# GPIO_Expander.net
KiCad netlist of a schematic drawn in Altium Designer
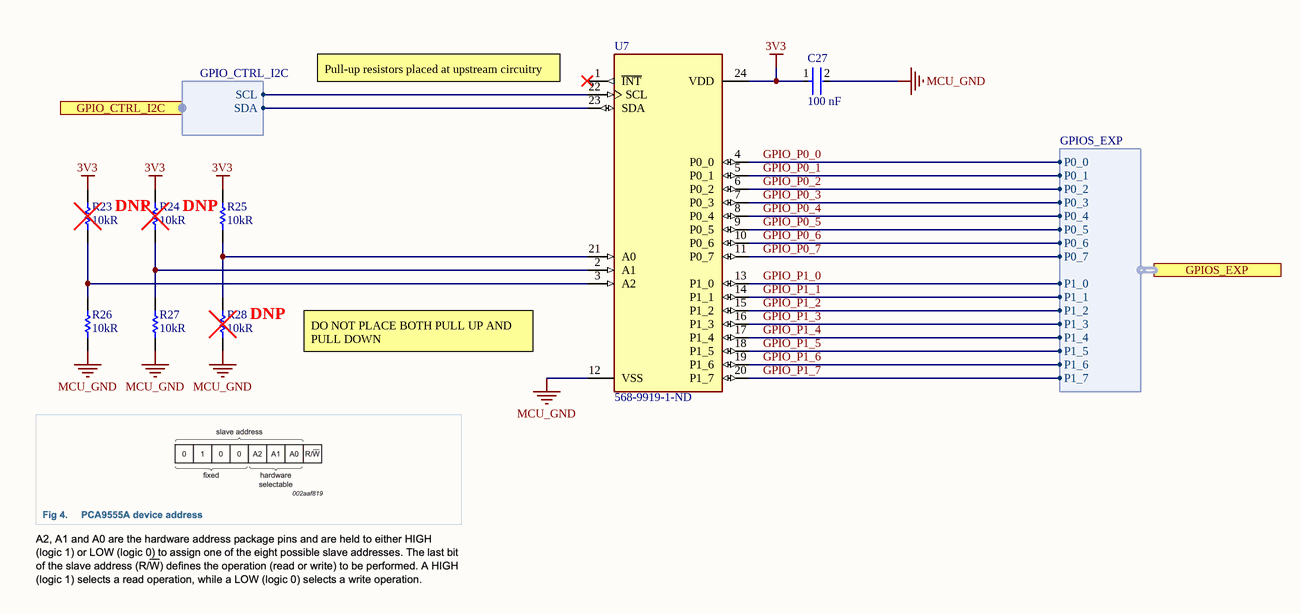
[diagram p0: GPIO_Expander.SchDoc]

(export (version "E")
  (design (tool "Eeschema 10.0.6"))
  (components
    (comp (ref "C27")
      (value "CC0603KRX7R7BB104")
      (footprint "FP-CC0603-DA-MFG")
      (description "CAP CER 0.1UF 16V X7R 0603")
      (fields
        (field (name "OCTOPART") "https://octopart.com/cc0603krx7r7bb104-yageo-192941")
        (field (name "TOLERANCE") "0.1")
        (field (name "CAPACITANCE") "100 nF")
      )
      (libsource (lib "Altium Content Vault") (part "11868f565c42a9108669ba33697ecf6"))
    )
    (comp (ref "R23")
      (value "CRCW060310K0FKEA")
      (footprint "RESC1609X50X30NL8T20")
      (description "Chip Resistor, 10 KOhm, +/- 1%, 100 mW, -55 to 155 degC, 0603 (1608 Metric), RoHS, Tape and Reel")
      (fields (field (name "MANUFACTURER") "Vishay Semiconductor") (field (name "RESISTANCE") "10kR"))
      (libsource (lib "Altium Content Vault") (part "RES-2"))
    )
    (comp (ref "R24")
      (value "CRCW060310K0FKEA")
      (footprint "RESC1609X50X30NL8T20")
      (description "Chip Resistor, 10 KOhm, +/- 1%, 100 mW, -55 to 155 degC, 0603 (1608 Metric), RoHS, Tape and Reel")
      (fields (field (name "MANUFACTURER") "Vishay Semiconductor") (field (name "RESISTANCE") "10kR"))
      (libsource (lib "Altium Content Vault") (part "RES-2"))
    )
    (comp (ref "R25")
      (value "CRCW060310K0FKEA")
      (footprint "RESC1609X50X30NL8T20")
      (description "Chip Resistor, 10 KOhm, +/- 1%, 100 mW, -55 to 155 degC, 0603 (1608 Metric), RoHS, Tape and Reel")
      (fields (field (name "MANUFACTURER") "Vishay Semiconductor") (field (name "RESISTANCE") "10kR"))
      (libsource (lib "Altium Content Vault") (part "RES-2"))
    )
    (comp (ref "R26")
      (value "CRCW060310K0FKEA")
      (footprint "RESC1609X50X30NL8T20")
      (description "Chip Resistor, 10 KOhm, +/- 1%, 100 mW, -55 to 155 degC, 0603 (1608 Metric), RoHS, Tape and Reel")
      (fields (field (name "MANUFACTURER") "Vishay Semiconductor") (field (name "RESISTANCE") "10kR"))
      (libsource (lib "Altium Content Vault") (part "RES-2"))
    )
    (comp (ref "R27")
      (value "CRCW060310K0FKEA")
      (footprint "RESC1609X50X30NL8T20")
      (description "Chip Resistor, 10 KOhm, +/- 1%, 100 mW, -55 to 155 degC, 0603 (1608 Metric), RoHS, Tape and Reel")
      (fields (field (name "MANUFACTURER") "Vishay Semiconductor") (field (name "RESISTANCE") "10kR"))
      (libsource (lib "Altium Content Vault") (part "RES-2"))
    )
    (comp (ref "R28")
      (value "CRCW060310K0FKEA")
      (footprint "RESC1609X50X30NL8T20")
      (description "Chip Resistor, 10 KOhm, +/- 1%, 100 mW, -55 to 155 degC, 0603 (1608 Metric), RoHS, Tape and Reel")
      (fields (field (name "MANUFACTURER") "Vishay Semiconductor") (field (name "RESISTANCE") "10kR"))
      (libsource (lib "Altium Content Vault") (part "RES-2"))
    )
    (comp (ref "U7")
      (value "568-9919-1-ND")
      (footprint "SOP65P640X110-24N")
      (description "Parallel I/O Port, 16-Bit, 16 I/O, CMOS, PDSO24")
      (fields
        (field (name "MANUFACTURER") "NXP Semiconductors")
        (field (name "MANUFACTURER PART NUMBER") "PCA9555APW,118")
        (field (name "SUPPLIER PART NUMBER 1") "568-9919-1-ND")
      )
      (libsource (lib "Schlib2") (part "PCA9555APW,118"))
    )
  )
  (nets
    (net (code "3") (name "/GPIO_P0_0") (class "Default")
      (node (ref "U7") (pin "4") (pinfunction "P0_0_4") (pintype "bidirectional"))
    )
    (net (code "4") (name "/GPIO_P0_1") (class "Default")
      (node (ref "U7") (pin "5") (pinfunction "P0_1_5") (pintype "bidirectional"))
    )
    (net (code "5") (name "/GPIO_P0_2") (class "Default")
      (node (ref "U7") (pin "6") (pinfunction "P0_2_6") (pintype "bidirectional"))
    )
    (net (code "6") (name "/GPIO_P0_3") (class "Default")
      (node (ref "U7") (pin "7") (pinfunction "P0_3_7") (pintype "bidirectional"))
    )
    (net (code "7") (name "/GPIO_P0_4") (class "Default")
      (node (ref "U7") (pin "8") (pinfunction "P0_4_8") (pintype "bidirectional"))
    )
    (net (code "8") (name "/GPIO_P0_5") (class "Default")
      (node (ref "U7") (pin "9") (pinfunction "P0_5_9") (pintype "bidirectional"))
    )
    (net (code "9") (name "/GPIO_P0_6") (class "Default")
      (node (ref "U7") (pin "10") (pinfunction "P0_6_10") (pintype "bidirectional"))
    )
    (net (code "10") (name "/GPIO_P0_7") (class "Default")
      (node (ref "U7") (pin "11") (pinfunction "P0_7_11") (pintype "bidirectional"))
    )
    (net (code "11") (name "/GPIO_P1_0") (class "Default")
      (node (ref "U7") (pin "13") (pinfunction "P1_0_13") (pintype "bidirectional"))
    )
    (net (code "12") (name "/GPIO_P1_1") (class "Default")
      (node (ref "U7") (pin "14") (pinfunction "P1_1_14") (pintype "bidirectional"))
    )
    (net (code "13") (name "/GPIO_P1_2") (class "Default")
      (node (ref "U7") (pin "15") (pinfunction "P1_2_15") (pintype "bidirectional"))
    )
    (net (code "14") (name "/GPIO_P1_3") (class "Default")
      (node (ref "U7") (pin "16") (pinfunction "P1_3_16") (pintype "bidirectional"))
    )
    (net (code "15") (name "/GPIO_P1_4") (class "Default")
      (node (ref "U7") (pin "17") (pinfunction "P1_4_17") (pintype "bidirectional"))
    )
    (net (code "16") (name "/GPIO_P1_5") (class "Default")
      (node (ref "U7") (pin "18") (pinfunction "P1_5_18") (pintype "bidirectional"))
    )
    (net (code "17") (name "/GPIO_P1_6") (class "Default")
      (node (ref "U7") (pin "19") (pinfunction "P1_6_19") (pintype "bidirectional"))
    )
    (net (code "18") (name "/GPIO_P1_7") (class "Default")
      (node (ref "U7") (pin "20") (pinfunction "P1_7_20") (pintype "bidirectional"))
    )
    (net (code "19") (name "/SCL") (class "Default")
      (node (ref "U7") (pin "22") (pinfunction "SCL_22") (pintype "input"))
    )
    (net (code "20") (name "/SDA") (class "Default")
      (node (ref "U7") (pin "23") (pinfunction "SDA_23") (pintype "bidirectional"))
    )
    (net (code "23") (name "3V3") (class "Default")
      (node (ref "C27") (pin "1") (pinfunction "1_1") (pintype "passive"))
      (node (ref "R23") (pin "2") (pinfunction "2_2") (pintype "passive"))
      (node (ref "R24") (pin "2") (pinfunction "2_2") (pintype "passive"))
      (node (ref "R25") (pin "2") (pinfunction "2_2") (pintype "passive"))
      (node (ref "U7") (pin "24") (pinfunction "VDD_24") (pintype "power_in"))
    )
    (net (code "24") (name "MCU_GND") (class "Default")
      (node (ref "C27") (pin "2") (pinfunction "2_2") (pintype "passive"))
      (node (ref "R26") (pin "1") (pinfunction "1_1") (pintype "passive"))
      (node (ref "R27") (pin "1") (pinfunction "1_1") (pintype "passive"))
      (node (ref "R28") (pin "1") (pinfunction "1_1") (pintype "passive"))
      (node (ref "U7") (pin "12") (pinfunction "VSS_12") (pintype "power_in"))
    )
    (net (code "25") (name "Net-(U7-A0)") (class "Default")
      (node (ref "R25") (pin "1") (pinfunction "1_1") (pintype "passive"))
      (node (ref "R28") (pin "2") (pinfunction "2_2") (pintype "passive"))
      (node (ref "U7") (pin "21") (pinfunction "A0_21") (pintype "input"))
    )
    (net (code "26") (name "Net-(U7-A1)") (class "Default")
      (node (ref "R24") (pin "1") (pinfunction "1_1") (pintype "passive"))
      (node (ref "R27") (pin "2") (pinfunction "2_2") (pintype "passive"))
      (node (ref "U7") (pin "2") (pinfunction "A1_2") (pintype "input"))
    )
    (net (code "27") (name "Net-(U7-A2)") (class "Default")
      (node (ref "R23") (pin "1") (pinfunction "1_1") (pintype "passive"))
      (node (ref "R26") (pin "2") (pinfunction "2_2") (pintype "passive"))
      (node (ref "U7") (pin "3") (pinfunction "A2_3") (pintype "input"))
    )
    (net (code "28") (name "unconnected-(U7-~{INT}-Pad1)") (class "Default")
      (node (ref "U7") (pin "1") (pinfunction "~{INT}_1") (pintype "output+no_connect"))
    )
  )
)
